# QUTMS-TSAL-S02.net
KiCad netlist of a schematic drawn in Altium Designer
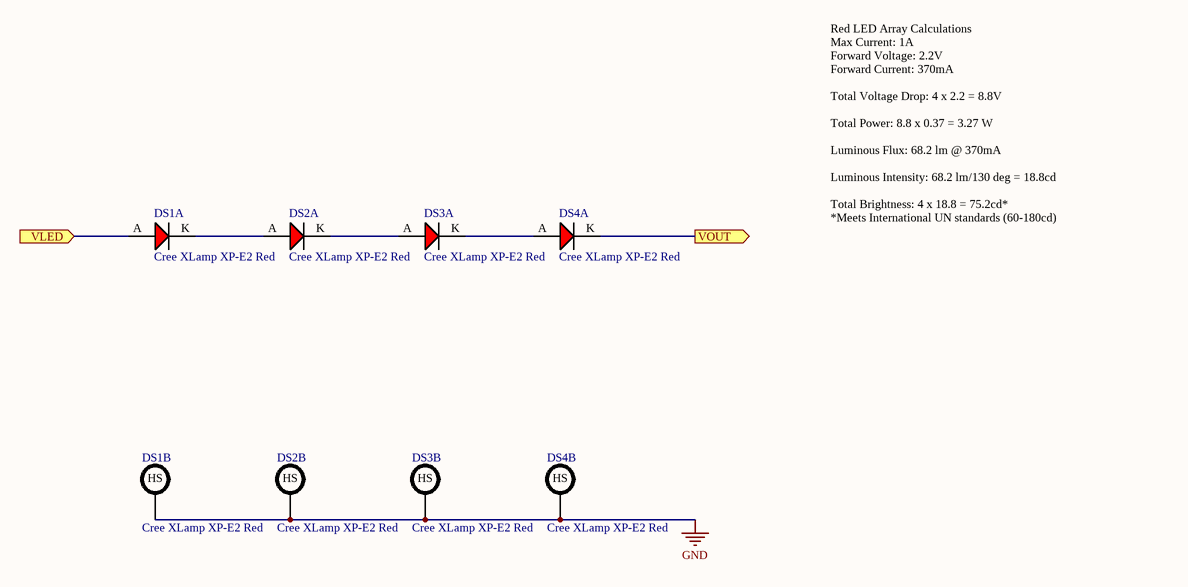
[diagram p0: QUTMS-TSAL-S02.SchDoc]

(export (version "E")
  (design (tool "Eeschema 10.0.6"))
  (components
    (comp (ref "DS1")
      (value "Cree XLamp XP-E2 Red")
      (footprint "Cree XLamp XP-E2")
      (description "XPEBRD-L1-0000-00601 -  High Brightness LED, XLamp XP-E2 Series, Red, 630 nm, 130 °, 62 lm, 1 A")
      (libsource (lib "QUTMS_LEDLibrary") (part "Cree XLamp XP-E2 Red"))
    )
    (comp (ref "DS2")
      (value "Cree XLamp XP-E2 Red")
      (footprint "Cree XLamp XP-E2")
      (description "XPEBRD-L1-0000-00601 -  High Brightness LED, XLamp XP-E2 Series, Red, 630 nm, 130 °, 62 lm, 1 A")
      (libsource (lib "QUTMS_LEDLibrary") (part "Cree XLamp XP-E2 Red"))
    )
    (comp (ref "DS3")
      (value "Cree XLamp XP-E2 Red")
      (footprint "Cree XLamp XP-E2")
      (description "XPEBRD-L1-0000-00601 -  High Brightness LED, XLamp XP-E2 Series, Red, 630 nm, 130 °, 62 lm, 1 A")
      (libsource (lib "QUTMS_LEDLibrary") (part "Cree XLamp XP-E2 Red"))
    )
    (comp (ref "DS4")
      (value "Cree XLamp XP-E2 Red")
      (footprint "Cree XLamp XP-E2")
      (description "XPEBRD-L1-0000-00601 -  High Brightness LED, XLamp XP-E2 Series, Red, 630 nm, 130 °, 62 lm, 1 A")
      (libsource (lib "QUTMS_LEDLibrary") (part "Cree XLamp XP-E2 Red"))
    )
  )
  (nets
    (net (code "1") (name "/VLED") (class "Default")
      (node (ref "DS1") (pin "A") (pinfunction "A_A") (pintype "passive"))
    )
    (net (code "2") (name "/VOUT") (class "Default")
      (node (ref "DS4") (pin "K") (pinfunction "K_K") (pintype "passive"))
    )
    (net (code "3") (name "GND") (class "Default")
      (node (ref "DS1") (pin "HS") (pinfunction "HS_HS") (pintype "passive"))
      (node (ref "DS2") (pin "HS") (pinfunction "HS_HS") (pintype "passive"))
      (node (ref "DS3") (pin "HS") (pinfunction "HS_HS") (pintype "passive"))
      (node (ref "DS4") (pin "HS") (pinfunction "HS_HS") (pintype "passive"))
    )
    (net (code "4") (name "Net-(DS1-PadK)") (class "Default")
      (node (ref "DS1") (pin "K") (pinfunction "K_K") (pintype "passive"))
      (node (ref "DS2") (pin "A") (pinfunction "A_A") (pintype "passive"))
    )
    (net (code "5") (name "Net-(DS2-PadK)") (class "Default")
      (node (ref "DS2") (pin "K") (pinfunction "K_K") (pintype "passive"))
      (node (ref "DS3") (pin "A") (pinfunction "A_A") (pintype "passive"))
    )
    (net (code "6") (name "Net-(DS3-PadK)") (class "Default")
      (node (ref "DS3") (pin "K") (pinfunction "K_K") (pintype "passive"))
      (node (ref "DS4") (pin "A") (pinfunction "A_A") (pintype "passive"))
    )
  )
)
